# pcb_balun_bottom_notch.net
KiCad netlist of a schematic drawn in EAGLE
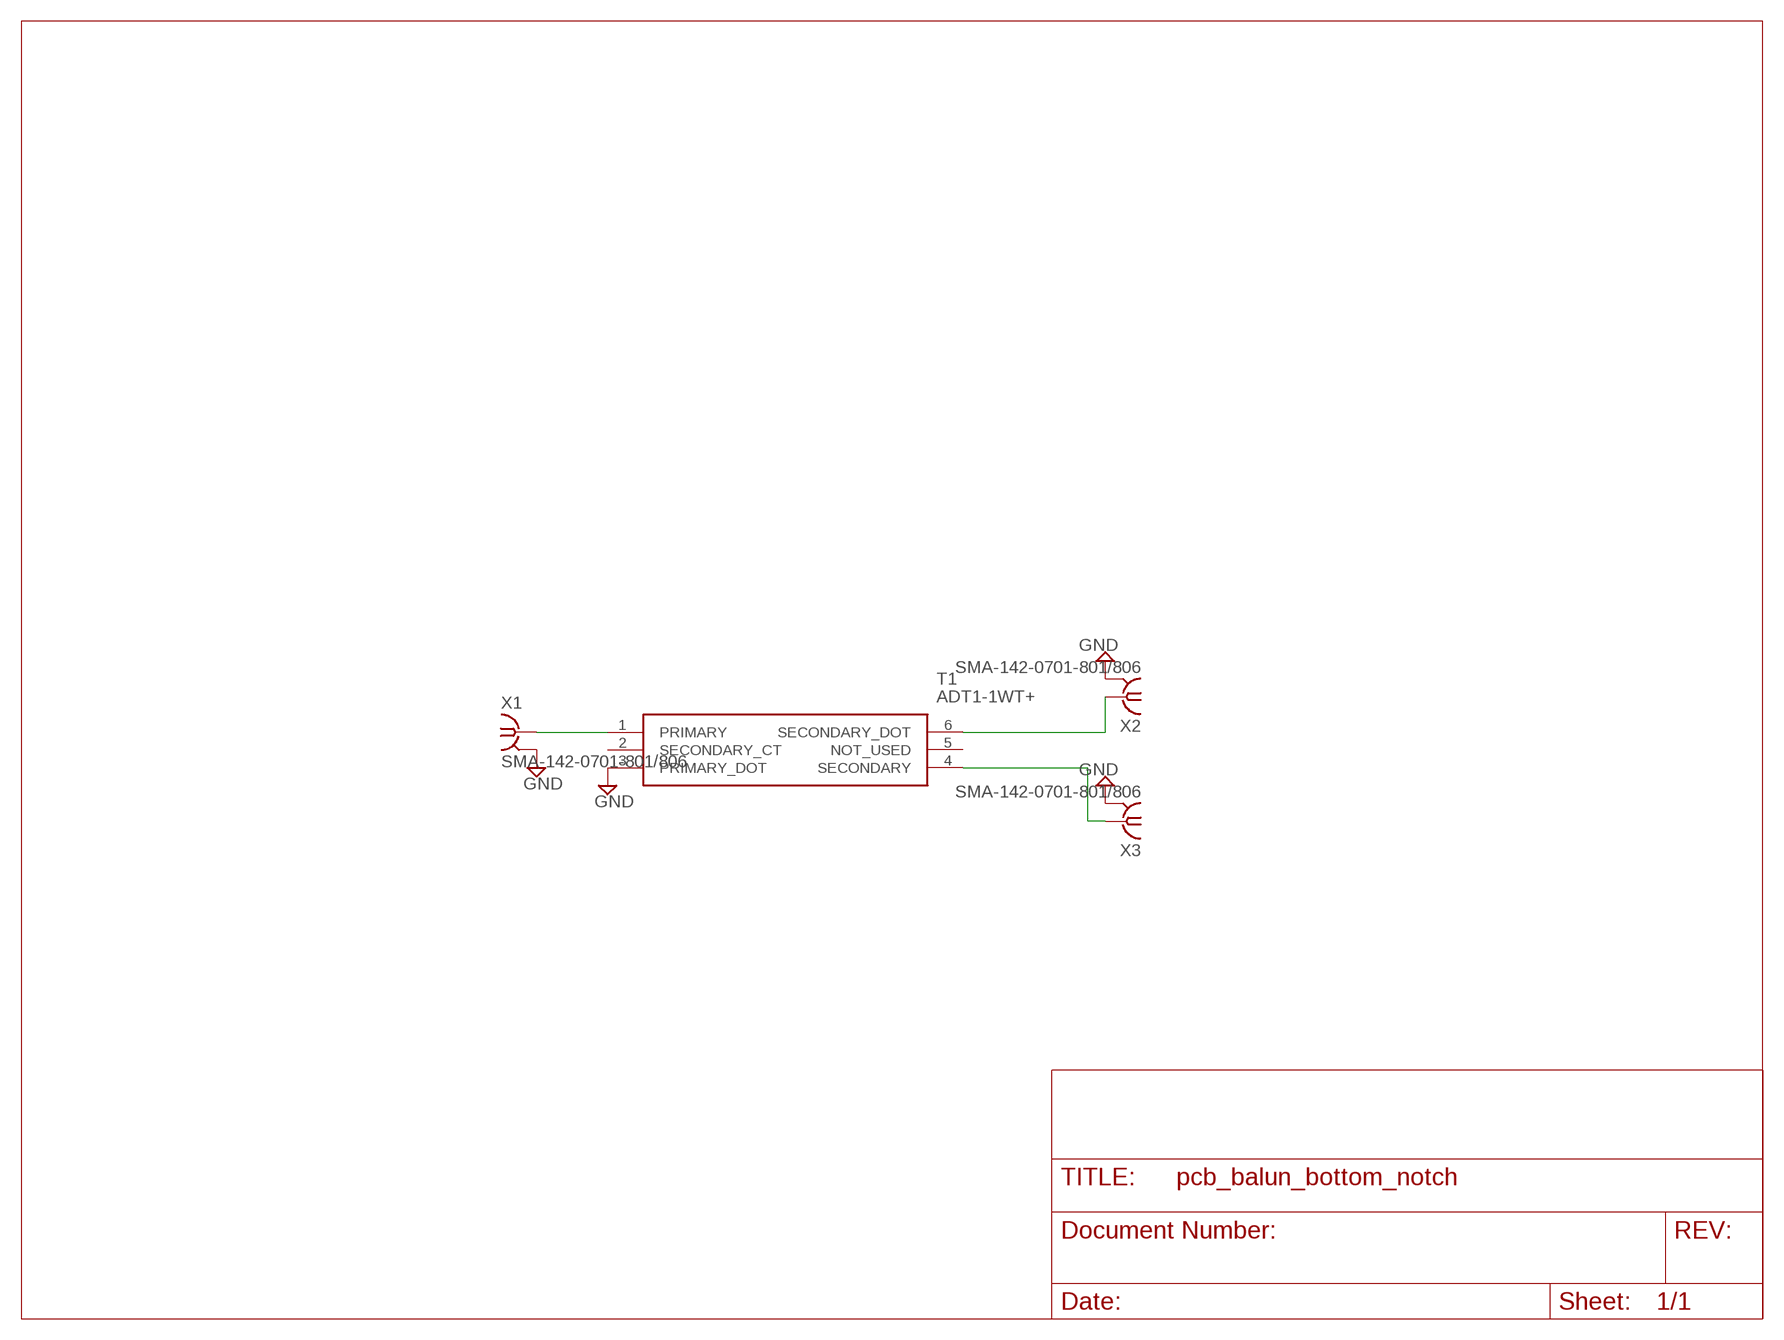
[diagram p0: schematic, sheet 1]

(export (version "E")
  (design (tool "Eeschema 10.0.6"))
  (components
    (comp (ref "T1")
      (value "ADT1-1WT+")
      (footprint "eagle-import:ADT11WT")
      (fields (field (name "MOUSER_PART_NUMBER") "139-ADT1-1WT"))
      (libsource (lib "eagle-import") (part "ADT1-1WT+"))
    )
    (comp (ref "X1")
      (value "SMA-142-0701-801/806")
      (footprint "eagle-import:J502-ND-142-0701-801_806")
      (fields (field (name "MF") "JOHNSON COMPONENTS") (field (name "MPN") "142-0701-801"))
      (libsource (lib "eagle-import") (part "con-coax_flange_mount_edit_SMA-142-0701-801/806"))
    )
    (comp (ref "X2")
      (value "SMA-142-0701-801/806")
      (footprint "eagle-import:J502-ND-142-0701-801_806")
      (fields (field (name "MF") "JOHNSON COMPONENTS") (field (name "MPN") "142-0701-801"))
      (libsource (lib "eagle-import") (part "SMA-142-0701-801/806"))
    )
    (comp (ref "X3")
      (value "SMA-142-0701-801/806")
      (footprint "eagle-import:J502-ND-142-0701-801_806")
      (fields (field (name "MF") "JOHNSON COMPONENTS") (field (name "MPN") "142-0701-801"))
      (libsource (lib "eagle-import") (part "SMA-142-0701-801/806"))
    )
  )
  (nets
    (net (code "1") (name "GND") (class "Default")
      (node (ref "T1") (pin "3") (pinfunction "PRIMARY_DOT_3") (pintype "bidirectional"))
      (node (ref "X1") (pin "G@1") (pinfunction "2_G@1") (pintype "passive"))
      (node (ref "X1") (pin "G@2") (pinfunction "2_G@2") (pintype "passive"))
      (node (ref "X1") (pin "G@3") (pinfunction "2_G@3") (pintype "passive"))
      (node (ref "X1") (pin "G@4") (pinfunction "2_G@4") (pintype "passive"))
      (node (ref "X2") (pin "G@1") (pinfunction "2_G@1") (pintype "passive"))
      (node (ref "X2") (pin "G@2") (pinfunction "2_G@2") (pintype "passive"))
      (node (ref "X2") (pin "G@3") (pinfunction "2_G@3") (pintype "passive"))
      (node (ref "X2") (pin "G@4") (pinfunction "2_G@4") (pintype "passive"))
      (node (ref "X3") (pin "G@1") (pinfunction "2_G@1") (pintype "passive"))
      (node (ref "X3") (pin "G@2") (pinfunction "2_G@2") (pintype "passive"))
      (node (ref "X3") (pin "G@3") (pinfunction "2_G@3") (pintype "passive"))
      (node (ref "X3") (pin "G@4") (pinfunction "2_G@4") (pintype "passive"))
    )
    (net (code "2") (name "Net-(T1-PRIMARY)") (class "Default")
      (node (ref "T1") (pin "1") (pinfunction "PRIMARY_1") (pintype "bidirectional"))
      (node (ref "X1") (pin "1") (pinfunction "1_1") (pintype "passive"))
    )
    (net (code "3") (name "Net-(T1-SECONDARY)") (class "Default")
      (node (ref "T1") (pin "4") (pinfunction "SECONDARY_4") (pintype "bidirectional"))
      (node (ref "X3") (pin "1") (pinfunction "1_1") (pintype "passive"))
    )
    (net (code "4") (name "Net-(T1-SECONDARY_DOT)") (class "Default")
      (node (ref "T1") (pin "6") (pinfunction "SECONDARY_DOT_6") (pintype "bidirectional"))
      (node (ref "X2") (pin "1") (pinfunction "1_1") (pintype "passive"))
    )
    (net (code "5") (name "unconnected-(T1-NOT_USED-Pad5)") (class "Default")
      (node (ref "T1") (pin "5") (pinfunction "NOT_USED_5") (pintype "bidirectional"))
    )
    (net (code "6") (name "unconnected-(T1-SECONDARY_CT-Pad2)") (class "Default")
      (node (ref "T1") (pin "2") (pinfunction "SECONDARY_CT_2") (pintype "bidirectional"))
    )
  )
)
